# Power_Supplies.net
KiCad netlist of a schematic drawn in Altium Designer
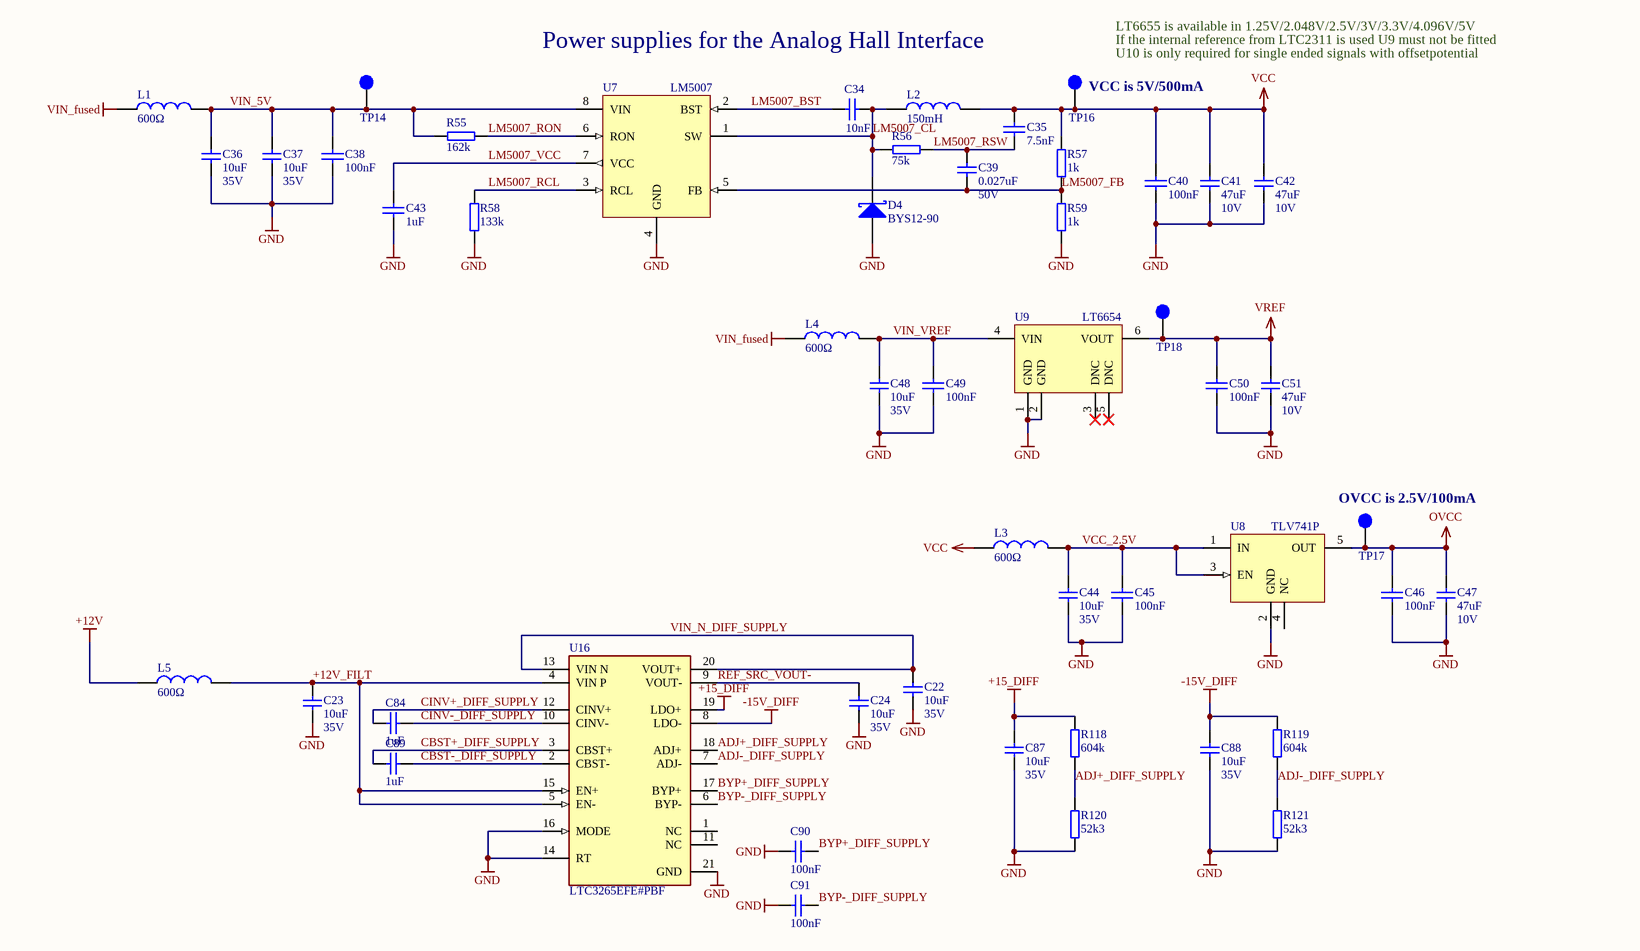
[diagram p0: Power Supplies.SchDoc]

(export (version "E")
  (design (tool "Eeschema 10.0.6"))
  (components
    (comp (ref "C22")
      (value "10uF")
      (footprint "C_1206")
      (description "Capacitor 1206")
      (fields
        (field (name "TOLERANCE") "10%")
        (field (name "MF") "Murata Electronics")
        (field (name "VOLTAGE") "35V")
        (field (name "CREATED") "2018_06_25_AGeiger")
      )
      (libsource (lib "UltraZohm_ADC") (part "C_1206"))
    )
    (comp (ref "C23")
      (value "10uF")
      (footprint "C_1206")
      (description "Capacitor 1206")
      (fields
        (field (name "TOLERANCE") "10%")
        (field (name "MF") "Murata Electronics")
        (field (name "VOLTAGE") "35V")
        (field (name "CREATED") "2018_06_25_AGeiger")
      )
      (libsource (lib "UltraZohm_ADC") (part "C_1206"))
    )
    (comp (ref "C24")
      (value "10uF")
      (footprint "C_1206")
      (description "Capacitor 1206")
      (fields
        (field (name "TOLERANCE") "10%")
        (field (name "MF") "Murata Electronics")
        (field (name "VOLTAGE") "35V")
        (field (name "CREATED") "2018_06_25_AGeiger")
      )
      (libsource (lib "UltraZohm_ADC") (part "C_1206"))
    )
    (comp (ref "C34")
      (value "10nF")
      (footprint "CAPC1608X07N")
      (fields (field (name "MF") "Würth") (field (name "MPN") "885012206065") (field (name "VOLTAGE") "25V"))
      (libsource (lib "UltraZohm_ADC") (part "Cap_0603"))
    )
    (comp (ref "C35")
      (value "7.5nF")
      (footprint "CAPC1608X07N")
      (fields
        (field (name "MF") "KEMET")
        (field (name "MPN") "C0603C752J3GACTU")
        (field (name "VOLTAGE") "25V")
      )
      (libsource (lib "UltraZohm_ADC") (part "Cap_0603"))
    )
    (comp (ref "C36")
      (value "10uF")
      (footprint "C_1206")
      (description "Capacitor 1206")
      (fields
        (field (name "TOLERANCE") "10%")
        (field (name "MF") "Murata Electronics")
        (field (name "VOLTAGE") "35V")
        (field (name "CREATED") "2018_06_25_AGeiger")
      )
      (libsource (lib "UltraZohm_ADC") (part "C_1206"))
    )
    (comp (ref "C37")
      (value "10uF")
      (footprint "C_1206")
      (description "Capacitor 1206")
      (fields
        (field (name "TOLERANCE") "10%")
        (field (name "MF") "Murata Electronics")
        (field (name "VOLTAGE") "35V")
        (field (name "CREATED") "2018_06_25_AGeiger")
      )
      (libsource (lib "UltraZohm_ADC") (part "C_1206"))
    )
    (comp (ref "C38")
      (value "100nF")
      (footprint "CAPC1608X07N")
      (fields (field (name "MF") "Würth") (field (name "MPN") "885012206071") (field (name "VOLTAGE") "25V"))
      (libsource (lib "UltraZohm_ADC") (part "Cap_0603"))
    )
    (comp (ref "C39")
      (value "0.027uF")
      (footprint "C_1206")
      (description "Capacitor 1206")
      (fields
        (field (name "TOLERANCE") "5%")
        (field (name "MF") "Murata")
        (field (name "VOLTAGE") "50V")
        (field (name "CREATED") "2018_06_25_AGeiger")
      )
      (libsource (lib "UltraZohm_ADC") (part "C_1206"))
    )
    (comp (ref "C40")
      (value "100nF")
      (footprint "CAPC1608X07N")
      (fields (field (name "MF") "Würth") (field (name "MPN") "885012206071") (field (name "VOLTAGE") "25V"))
      (libsource (lib "UltraZohm_ADC") (part "Cap_0603"))
    )
    (comp (ref "C41")
      (value "47uF")
      (footprint "C_1206")
      (description "Capacitor 1206")
      (fields
        (field (name "TOLERANCE") "10%")
        (field (name "MF") "Murata Electronics")
        (field (name "VOLTAGE") "10V")
        (field (name "CREATED") "2018_06_25_AGeiger")
      )
      (libsource (lib "UltraZohm_ADC") (part "C_1206"))
    )
    (comp (ref "C42")
      (value "47uF")
      (footprint "C_1206")
      (description "Capacitor 1206")
      (fields
        (field (name "TOLERANCE") "10%")
        (field (name "MF") "Murata Electronics")
        (field (name "VOLTAGE") "10V")
        (field (name "CREATED") "2018_06_25_AGeiger")
      )
      (libsource (lib "UltraZohm_ADC") (part "C_1206"))
    )
    (comp (ref "C43")
      (value "1uF")
      (footprint "CAPC1608X07N")
      (fields (field (name "MPN") "C0603C105K3R") (field (name "VOLTAGE") "25V"))
      (libsource (lib "UltraZohm_ADC") (part "Cap_0603"))
    )
    (comp (ref "C44")
      (value "10uF")
      (footprint "C_1206")
      (description "Capacitor 1206")
      (fields
        (field (name "TOLERANCE") "10%")
        (field (name "MF") "Murata Electronics")
        (field (name "VOLTAGE") "35V")
        (field (name "CREATED") "2018_06_25_AGeiger")
      )
      (libsource (lib "UltraZohm_ADC") (part "C_1206"))
    )
    (comp (ref "C45")
      (value "100nF")
      (footprint "CAPC1608X07N")
      (fields (field (name "MF") "Würth") (field (name "MPN") "885012206071") (field (name "VOLTAGE") "25V"))
      (libsource (lib "UltraZohm_ADC") (part "Cap_0603"))
    )
    (comp (ref "C46")
      (value "100nF")
      (footprint "CAPC1608X07N")
      (fields (field (name "MF") "Würth") (field (name "MPN") "885012206071") (field (name "VOLTAGE") "25V"))
      (libsource (lib "UltraZohm_ADC") (part "Cap_0603"))
    )
    (comp (ref "C47")
      (value "47uF")
      (footprint "C_1206")
      (description "Capacitor 1206")
      (fields
        (field (name "TOLERANCE") "10%")
        (field (name "MF") "Murata Electronics")
        (field (name "VOLTAGE") "10V")
        (field (name "CREATED") "2018_06_25_AGeiger")
      )
      (libsource (lib "UltraZohm_ADC") (part "C_1206"))
    )
    (comp (ref "C48")
      (value "10uF")
      (footprint "C_1206")
      (description "Capacitor 1206")
      (fields
        (field (name "TOLERANCE") "10%")
        (field (name "MF") "Murata Electronics")
        (field (name "VOLTAGE") "35V")
        (field (name "CREATED") "2018_06_25_AGeiger")
      )
      (libsource (lib "UltraZohm_ADC") (part "C_1206"))
    )
    (comp (ref "C49")
      (value "100nF")
      (footprint "CAPC1608X07N")
      (fields (field (name "MF") "Würth") (field (name "MPN") "885012206071") (field (name "VOLTAGE") "25V"))
      (libsource (lib "UltraZohm_ADC") (part "Cap_0603"))
    )
    (comp (ref "C50")
      (value "100nF")
      (footprint "CAPC1608X07N")
      (fields (field (name "MF") "Würth") (field (name "MPN") "885012206071") (field (name "VOLTAGE") "25V"))
      (libsource (lib "UltraZohm_ADC") (part "Cap_0603"))
    )
    (comp (ref "C51")
      (value "47uF")
      (footprint "C_1206")
      (description "Capacitor 1206")
      (fields
        (field (name "TOLERANCE") "10%")
        (field (name "MF") "Murata Electronics")
        (field (name "VOLTAGE") "10V")
        (field (name "CREATED") "2018_06_25_AGeiger")
      )
      (libsource (lib "UltraZohm_ADC") (part "C_1206"))
    )
    (comp (ref "C84")
      (value "1uF")
      (footprint "CAPC1608X07N")
      (fields (field (name "MPN") "C0603C105K3R") (field (name "VOLTAGE") "25V"))
      (libsource (lib "UltraZohm_ADC") (part "Cap_0603"))
    )
    (comp (ref "C87")
      (value "10uF")
      (footprint "C_1206")
      (description "Capacitor 1206")
      (fields
        (field (name "TOLERANCE") "10%")
        (field (name "MF") "Murata Electronics")
        (field (name "VOLTAGE") "35V")
        (field (name "CREATED") "2018_06_25_AGeiger")
      )
      (libsource (lib "UltraZohm_ADC") (part "C_1206"))
    )
    (comp (ref "C88")
      (value "10uF")
      (footprint "C_1206")
      (description "Capacitor 1206")
      (fields
        (field (name "TOLERANCE") "10%")
        (field (name "MF") "Murata Electronics")
        (field (name "VOLTAGE") "35V")
        (field (name "CREATED") "2018_06_25_AGeiger")
      )
      (libsource (lib "UltraZohm_ADC") (part "C_1206"))
    )
    (comp (ref "C89")
      (value "1uF")
      (footprint "CAPC1608X07N")
      (fields (field (name "MPN") "C0603C105K3R") (field (name "VOLTAGE") "25V"))
      (libsource (lib "UltraZohm_ADC") (part "Cap_0603"))
    )
    (comp (ref "C90")
      (value "100nF")
      (footprint "CAPC1608X07N")
      (fields (field (name "MF") "Würth") (field (name "MPN") "885012206071") (field (name "VOLTAGE") "25V"))
      (libsource (lib "UltraZohm_ADC") (part "Cap_0603"))
    )
    (comp (ref "C91")
      (value "100nF")
      (footprint "CAPC1608X07N")
      (fields (field (name "MF") "Würth") (field (name "MPN") "885012206071") (field (name "VOLTAGE") "25V"))
      (libsource (lib "UltraZohm_ADC") (part "Cap_0603"))
    )
    (comp (ref "D4")
      (value "BYS12-90")
      (footprint "DIOM4227X23N")
      (description "Schottky Diode")
      (fields (field (name "MF") "Vishay") (field (name "MPN") "BYS12-90-E3/TR3"))
      (libsource (lib "UltraZohm_ADC") (part "BYS12-90"))
    )
    (comp (ref "L1")
      (value "600Ω")
      (footprint "WE-CBF_0805_High Current")
      (description "WE-CBF SMD EMI Suppression Ferrite Bead, 0805, 600Ω")
      (fields (field (name "MF") "Wurth Elektronik") (field (name "MPN") "742792040"))
      (libsource (lib "UltraZohm_ADC") (part "WE-CBF, 742792040"))
    )
    (comp (ref "L2")
      (value "150mH")
      (footprint "SMT_inductor_1050_Performance")
      (description "SMT power Inductor, 150uH, 320m DRC")
      (fields (field (name "MF") "EPCOS / TDK") (field (name "MPN") "B82464G4154M"))
      (libsource (lib "UltraZohm_ADC") (part "B82464G4154M"))
    )
    (comp (ref "L3")
      (value "600Ω")
      (footprint "WE-CBF_0805_High Current")
      (description "WE-CBF SMD EMI Suppression Ferrite Bead, 0805, 600Ω")
      (fields (field (name "MF") "Wurth Elektronik") (field (name "MPN") "742792040"))
      (libsource (lib "UltraZohm_ADC") (part "WE-CBF, 742792040"))
    )
    (comp (ref "L4")
      (value "600Ω")
      (footprint "WE-CBF_0805_High Current")
      (description "WE-CBF SMD EMI Suppression Ferrite Bead, 0805, 600Ω")
      (fields (field (name "MF") "Wurth Elektronik") (field (name "MPN") "742792040"))
      (libsource (lib "UltraZohm_ADC") (part "WE-CBF, 742792040"))
    )
    (comp (ref "L5")
      (value "600Ω")
      (footprint "WE-CBF_0805_High Current")
      (description "WE-CBF SMD EMI Suppression Ferrite Bead, 0805, 600Ω")
      (fields (field (name "MF") "Wurth Elektronik") (field (name "MPN") "742792040"))
      (libsource (lib "UltraZohm_ADC") (part "WE-CBF, 742792040"))
    )
    (comp (ref "R55")
      (value "162k")
      (footprint "RESC1608X06N")
      (fields (field (name "MF") "Vishay") (field (name "MPN") "CRCW0603162KFKEA"))
      (libsource (lib "UltraZohm_ADC") (part "R_0603"))
    )
    (comp (ref "R56")
      (value "75k")
      (footprint "RESC1608X06N")
      (fields (field (name "MF") "Yageo") (field (name "MPN") "RC0603FR-0775KL"))
      (libsource (lib "UltraZohm_ADC") (part "R_0603"))
    )
    (comp (ref "R57")
      (value "1k")
      (footprint "RESC1608X06N")
      (fields (field (name "MF") "Yageo") (field (name "MPN") "RC0603FR-071KL"))
      (libsource (lib "UltraZohm_ADC") (part "R_0603"))
    )
    (comp (ref "R58")
      (value "133k")
      (footprint "RESC1608X06N")
      (fields (field (name "MF") "Yageo") (field (name "MPN") "RC0603FR-07133KL"))
      (libsource (lib "UltraZohm_ADC") (part "R_0603"))
    )
    (comp (ref "R59")
      (value "1k")
      (footprint "RESC1608X06N")
      (fields (field (name "MF") "Yageo") (field (name "MPN") "RC0603FR-071KL"))
      (libsource (lib "UltraZohm_ADC") (part "R_0603"))
    )
    (comp (ref "R118")
      (value "604k")
      (footprint "RESC1608X06N")
      (fields (field (name "MF") "Yageo") (field (name "MPN") "RC0603FR-071KL"))
      (libsource (lib "UltraZohm_ADC") (part "R_0603"))
    )
    (comp (ref "R119")
      (value "604k")
      (footprint "RESC1608X06N")
      (fields (field (name "MF") "Yageo") (field (name "MPN") "RC0603FR-071KL"))
      (libsource (lib "UltraZohm_ADC") (part "R_0603"))
    )
    (comp (ref "R120")
      (value "52k3")
      (footprint "RESC1608X06N")
      (fields (field (name "MF") "Yageo") (field (name "MPN") "RC0603FR-071KL"))
      (libsource (lib "UltraZohm_ADC") (part "R_0603"))
    )
    (comp (ref "R121")
      (value "52k3")
      (footprint "RESC1608X06N")
      (fields (field (name "MF") "Yageo") (field (name "MPN") "RC0603FR-071KL"))
      (libsource (lib "UltraZohm_ADC") (part "R_0603"))
    )
    (comp (ref "TP14")
      (value "VIN")
      (footprint "TP_1mm")
      (description "Testpoint 1mm")
      (fields (field (name "CREATED") "2018_06_25_AGeiger"))
      (libsource (lib "UltraZOhm_CarrierBoard") (part "TP_1mm"))
    )
    (comp (ref "TP16")
      (value "VCC")
      (footprint "TP_1mm")
      (description "Testpoint 1mm")
      (fields (field (name "CREATED") "2018_06_25_AGeiger"))
      (libsource (lib "UltraZOhm_CarrierBoard") (part "TP_1mm"))
    )
    (comp (ref "TP17")
      (value "OVCC")
      (footprint "TP_1mm")
      (description "Testpoint 1mm")
      (fields (field (name "CREATED") "2018_06_25_AGeiger"))
      (libsource (lib "UltraZOhm_CarrierBoard") (part "TP_1mm"))
    )
    (comp (ref "TP18")
      (value "VREF")
      (footprint "TP_1mm")
      (description "Testpoint 1mm")
      (fields (field (name "CREATED") "2018_06_25_AGeiger"))
      (libsource (lib "UltraZOhm_CarrierBoard") (part "TP_1mm"))
    )
    (comp (ref "U7")
      (value "LM5007")
      (footprint "TSOP65P490X110-8N")
      (description "Buck Converter, 9-75Vin, 2.5-73Vout")
      (fields (field (name "MF") "Texas Instruments") (field (name "MPN") "LM5007MM/NOPB"))
      (libsource (lib "UltraZohm_ADC") (part "LM5007"))
    )
    (comp (ref "U8")
      (value "TLV741P")
      (footprint "SOT95P250X110-5N")
      (description "150mA, 2.5V LDO")
      (fields (field (name "MF") "Texas Instruments") (field (name "MPN") "TLV74125PDBVR"))
      (libsource (lib "UltraZohm_ADC") (part "TLV741P"))
    )
    (comp (ref "U9")
      (value "LT6654")
      (footprint "SOT95P280X100-6N")
      (fields (field (name "MF") "Analog Devices") (field (name "MPN") "LT6654BIS6-5#TRMPBF"))
      (libsource (lib "UltraZohm_ADC") (part "LT6654"))
    )
    (comp (ref "U16")
      (value "LTC3265EFE#PBF")
      (footprint "FP-FE-20-05-08-1663-MFG")
      (description "IC REG CHARG PUMP INV DL 20TSSOP")
      (fields
        (field (name "OCTOPART") "https://octopart.com/ltc3265efe%23pbf-analog+devices-88944569")
        (field (name "MANUFACTURER") "Analog Devices Inc")
      )
      (libsource (lib "Altium Content Vault") (part "678dbf8bd1045e63ee41eb06a13e70f"))
    )
  )
  (nets
    (net (code "1") (name "+12V") (class "Default")
      (node (ref "L5") (pin "1") (pinfunction "1_1") (pintype "passive"))
    )
    (net (code "2") (name "+15_DIFF") (class "Default")
      (node (ref "C87") (pin "2") (pinfunction "2_2") (pintype "passive"))
      (node (ref "R118") (pin "2") (pintype "passive"))
      (node (ref "U16") (pin "19") (pinfunction "LDO+_19") (pintype "passive"))
    )
    (net (code "3") (name "-15V_DIFF") (class "Default")
      (node (ref "C88") (pin "2") (pinfunction "2_2") (pintype "passive"))
      (node (ref "R119") (pin "2") (pintype "passive"))
      (node (ref "U16") (pin "8") (pinfunction "LDO-_8") (pintype "passive"))
    )
    (net (code "4") (name "/+12V_FILT") (class "Default")
      (node (ref "C23") (pin "2") (pinfunction "2_2") (pintype "passive"))
      (node (ref "L5") (pin "2") (pinfunction "2_2") (pintype "passive"))
      (node (ref "U16") (pin "15") (pinfunction "EN+_15") (pintype "input"))
      (node (ref "U16") (pin "4") (pinfunction "VIN_P_4") (pintype "power_in"))
      (node (ref "U16") (pin "5") (pinfunction "EN-_5") (pintype "input"))
    )
    (net (code "5") (name "/ADJ+_DIFF_SUPPLY") (class "Default")
      (node (ref "R118") (pin "1") (pintype "passive"))
      (node (ref "R120") (pin "2") (pintype "passive"))
      (node (ref "U16") (pin "18") (pinfunction "ADJ+_18") (pintype "passive"))
    )
    (net (code "6") (name "/ADJ-_DIFF_SUPPLY") (class "Default")
      (node (ref "R119") (pin "1") (pintype "passive"))
      (node (ref "R121") (pin "2") (pintype "passive"))
      (node (ref "U16") (pin "7") (pinfunction "ADJ-_7") (pintype "passive"))
    )
    (net (code "7") (name "/BYP+_DIFF_SUPPLY") (class "Default")
      (node (ref "C90") (pin "1") (pinfunction "1_1") (pintype "passive"))
      (node (ref "U16") (pin "17") (pinfunction "BYP+_17") (pintype "passive"))
    )
    (net (code "8") (name "/BYP-_DIFF_SUPPLY") (class "Default")
      (node (ref "C91") (pin "1") (pinfunction "1_1") (pintype "passive"))
      (node (ref "U16") (pin "6") (pinfunction "BYP-_6") (pintype "passive"))
    )
    (net (code "9") (name "/CBST+_DIFF_SUPPLY") (class "Default")
      (node (ref "C89") (pin "1") (pinfunction "1_1") (pintype "passive"))
      (node (ref "U16") (pin "3") (pinfunction "CBST+_3") (pintype "passive"))
    )
    (net (code "10") (name "/CBST-_DIFF_SUPPLY") (class "Default")
      (node (ref "C89") (pin "2") (pinfunction "2_2") (pintype "passive"))
      (node (ref "U16") (pin "2") (pinfunction "CBST-_2") (pintype "passive"))
    )
    (net (code "11") (name "/CINV+_DIFF_SUPPLY") (class "Default")
      (node (ref "C84") (pin "1") (pinfunction "1_1") (pintype "passive"))
      (node (ref "U16") (pin "12") (pinfunction "CINV+_12") (pintype "passive"))
    )
    (net (code "12") (name "/CINV-_DIFF_SUPPLY") (class "Default")
      (node (ref "C84") (pin "2") (pinfunction "2_2") (pintype "passive"))
      (node (ref "U16") (pin "10") (pinfunction "CINV-_10") (pintype "passive"))
    )
    (net (code "13") (name "/LM5007_BST") (class "Default")
      (node (ref "C34") (pin "1") (pinfunction "1_1") (pintype "passive"))
      (node (ref "U7") (pin "2") (pinfunction "BST_2") (pintype "input"))
    )
    (net (code "14") (name "/LM5007_CL") (class "Default")
      (node (ref "C34") (pin "2") (pinfunction "2_2") (pintype "passive"))
      (node (ref "D4") (pin "1") (pinfunction "K_1") (pintype "passive"))
      (node (ref "L2") (pin "1") (pinfunction "1_1") (pintype "passive"))
      (node (ref "R56") (pin "1") (pintype "passive"))
      (node (ref "U7") (pin "1") (pinfunction "SW_1") (pintype "power_in"))
    )
    (net (code "15") (name "/LM5007_FB") (class "Default")
      (node (ref "C39") (pin "1") (pinfunction "1_1") (pintype "passive"))
      (node (ref "R57") (pin "1") (pintype "passive"))
      (node (ref "R59") (pin "2") (pintype "passive"))
      (node (ref "U7") (pin "5") (pinfunction "FB_5") (pintype "input"))
    )
    (net (code "16") (name "/LM5007_RCL") (class "Default")
      (node (ref "R58") (pin "2") (pintype "passive"))
      (node (ref "U7") (pin "3") (pinfunction "RCL_3") (pintype "input"))
    )
    (net (code "17") (name "/LM5007_RON") (class "Default")
      (node (ref "R55") (pin "2") (pintype "passive"))
      (node (ref "U7") (pin "6") (pinfunction "RON_6") (pintype "input"))
    )
    (net (code "18") (name "/LM5007_RSW") (class "Default")
      (node (ref "C35") (pin "2") (pinfunction "2_2") (pintype "passive"))
      (node (ref "C39") (pin "2") (pinfunction "2_2") (pintype "passive"))
      (node (ref "R56") (pin "2") (pintype "passive"))
    )
    (net (code "19") (name "/LM5007_VCC") (class "Default")
      (node (ref "C43") (pin "2") (pinfunction "2_2") (pintype "passive"))
      (node (ref "U7") (pin "7") (pinfunction "VCC_7") (pintype "output"))
    )
    (net (code "20") (name "/REF_SRC_VOUT-") (class "Default")
      (node (ref "C24") (pin "2") (pinfunction "2_2") (pintype "passive"))
      (node (ref "U16") (pin "9") (pinfunction "VOUT-_9") (pintype "power_in"))
    )
    (net (code "21") (name "/VCC_2.5V") (class "Default")
      (node (ref "C44") (pin "2") (pinfunction "2_2") (pintype "passive"))
      (node (ref "C45") (pin "1") (pinfunction "1_1") (pintype "passive"))
      (node (ref "L3") (pin "2") (pinfunction "2_2") (pintype "passive"))
      (node (ref "U8") (pin "1") (pinfunction "IN_1") (pintype "power_in"))
      (node (ref "U8") (pin "3") (pinfunction "EN_3") (pintype "input"))
    )
    (net (code "22") (name "/VIN_5V") (class "Default")
      (node (ref "C36") (pin "2") (pinfunction "2_2") (pintype "passive"))
      (node (ref "C37") (pin "2") (pinfunction "2_2") (pintype "passive"))
      (node (ref "C38") (pin "1") (pinfunction "1_1") (pintype "passive"))
      (node (ref "L1") (pin "2") (pinfunction "2_2") (pintype "passive"))
      (node (ref "R55") (pin "1") (pintype "passive"))
      (node (ref "TP14") (pin "1") (pintype "passive"))
      (node (ref "U7") (pin "8") (pinfunction "VIN_8") (pintype "power_in"))
    )
    (net (code "23") (name "/VIN_N_DIFF_SUPPLY") (class "Default")
      (node (ref "C22") (pin "2") (pinfunction "2_2") (pintype "passive"))
      (node (ref "U16") (pin "13") (pinfunction "VIN_N_13") (pintype "power_in"))
      (node (ref "U16") (pin "20") (pinfunction "VOUT+_20") (pintype "power_in"))
    )
    (net (code "24") (name "/VIN_VREF") (class "Default")
      (node (ref "C48") (pin "2") (pinfunction "2_2") (pintype "passive"))
      (node (ref "C49") (pin "1") (pinfunction "1_1") (pintype "passive"))
      (node (ref "L4") (pin "2") (pinfunction "2_2") (pintype "passive"))
      (node (ref "U9") (pin "4") (pinfunction "VIN_4") (pintype "power_in"))
    )
    (net (code "25") (name "GND") (class "Default")
      (node (ref "C22") (pin "1") (pinfunction "1_1") (pintype "passive"))
      (node (ref "C23") (pin "1") (pinfunction "1_1") (pintype "passive"))
      (node (ref "C24") (pin "1") (pinfunction "1_1") (pintype "passive"))
      (node (ref "C36") (pin "1") (pinfunction "1_1") (pintype "passive"))
      (node (ref "C37") (pin "1") (pinfunction "1_1") (pintype "passive"))
      (node (ref "C38") (pin "2") (pinfunction "2_2") (pintype "passive"))
      (node (ref "C40") (pin "1") (pinfunction "1_1") (pintype "passive"))
      (node (ref "C41") (pin "1") (pinfunction "1_1") (pintype "passive"))
      (node (ref "C42") (pin "1") (pinfunction "1_1") (pintype "passive"))
      (node (ref "C43") (pin "1") (pinfunction "1_1") (pintype "passive"))
      (node (ref "C44") (pin "1") (pinfunction "1_1") (pintype "passive"))
      (node (ref "C45") (pin "2") (pinfunction "2_2") (pintype "passive"))
      (node (ref "C46") (pin "2") (pinfunction "2_2") (pintype "passive"))
      (node (ref "C47") (pin "1") (pinfunction "1_1") (pintype "passive"))
      (node (ref "C48") (pin "1") (pinfunction "1_1") (pintype "passive"))
      (node (ref "C49") (pin "2") (pinfunction "2_2") (pintype "passive"))
      (node (ref "C50") (pin "2") (pinfunction "2_2") (pintype "passive"))
      (node (ref "C51") (pin "1") (pinfunction "1_1") (pintype "passive"))
      (node (ref "C87") (pin "1") (pinfunction "1_1") (pintype "passive"))
      (node (ref "C88") (pin "1") (pinfunction "1_1") (pintype "passive"))
      (node (ref "C90") (pin "2") (pinfunction "2_2") (pintype "passive"))
      (node (ref "C91") (pin "2") (pinfunction "2_2") (pintype "passive"))
      (node (ref "D4") (pin "2") (pinfunction "A_2") (pintype "passive"))
      (node (ref "R120") (pin "1") (pintype "passive"))
      (node (ref "R121") (pin "1") (pintype "passive"))
      (node (ref "R58") (pin "1") (pintype "passive"))
      (node (ref "R59") (pin "1") (pintype "passive"))
      (node (ref "U16") (pin "14") (pinfunction "RT_14") (pintype "passive"))
      (node (ref "U16") (pin "16") (pinfunction "MODE_16") (pintype "input"))
      (node (ref "U16") (pin "21") (pinfunction "GND_21") (pintype "power_in"))
      (node (ref "U7") (pin "4") (pinfunction "GND_4") (pintype "power_in"))
      (node (ref "U8") (pin "2") (pinfunction "GND_2") (pintype "power_in"))
      (node (ref "U9") (pin "1") (pinfunction "GND_1") (pintype "power_in"))
      (node (ref "U9") (pin "2") (pinfunction "GND_2") (pintype "power_in"))
    )
    (net (code "26") (name "OVCC") (class "Default")
      (node (ref "C46") (pin "1") (pinfunction "1_1") (pintype "passive"))
      (node (ref "C47") (pin "2") (pinfunction "2_2") (pintype "passive"))
      (node (ref "TP17") (pin "1") (pintype "passive"))
      (node (ref "U8") (pin "5") (pinfunction "OUT_5") (pintype "power_in"))
    )
    (net (code "27") (name "VCC") (class "Default")
      (node (ref "C35") (pin "1") (pinfunction "1_1") (pintype "passive"))
      (node (ref "C40") (pin "2") (pinfunction "2_2") (pintype "passive"))
      (node (ref "C41") (pin "2") (pinfunction "2_2") (pintype "passive"))
      (node (ref "C42") (pin "2") (pinfunction "2_2") (pintype "passive"))
      (node (ref "L2") (pin "2") (pinfunction "2_2") (pintype "passive"))
      (node (ref "L3") (pin "1") (pinfunction "1_1") (pintype "passive"))
      (node (ref "R57") (pin "2") (pintype "passive"))
      (node (ref "TP16") (pin "1") (pintype "passive"))
    )
    (net (code "28") (name "VIN_fused") (class "Default")
      (node (ref "L1") (pin "1") (pinfunction "1_1") (pintype "passive"))
      (node (ref "L4") (pin "1") (pinfunction "1_1") (pintype "passive"))
    )
    (net (code "29") (name "VREF") (class "Default")
      (node (ref "C50") (pin "1") (pinfunction "1_1") (pintype "passive"))
      (node (ref "C51") (pin "2") (pinfunction "2_2") (pintype "passive"))
      (node (ref "TP18") (pin "1") (pintype "passive"))
      (node (ref "U9") (pin "6") (pinfunction "VOUT_6") (pintype "power_in"))
    )
    (net (code "30") (name "unconnected-(U8-NC-Pad4)") (class "Default")
      (node (ref "U8") (pin "4") (pinfunction "NC_4") (pintype "passive"))
    )
    (net (code "31") (name "unconnected-(U9-DNC-Pad3)") (class "Default")
      (node (ref "U9") (pin "3") (pinfunction "DNC_3") (pintype "passive+no_connect"))
    )
    (net (code "32") (name "unconnected-(U9-DNC-Pad5)") (class "Default")
      (node (ref "U9") (pin "5") (pinfunction "DNC_5") (pintype "passive+no_connect"))
    )
    (net (code "33") (name "unconnected-(U16-NC-Pad1)") (class "Default")
      (node (ref "U16") (pin "1") (pinfunction "NC_1") (pintype "passive"))
    )
    (net (code "34") (name "unconnected-(U16-NC-Pad11)") (class "Default")
      (node (ref "U16") (pin "11") (pinfunction "NC_11") (pintype "passive"))
    )
  )
)
